# SCH_Atari_ST_sidecart_prototype_shared_b.net
KiCad netlist of a schematic drawn in EasyEDA
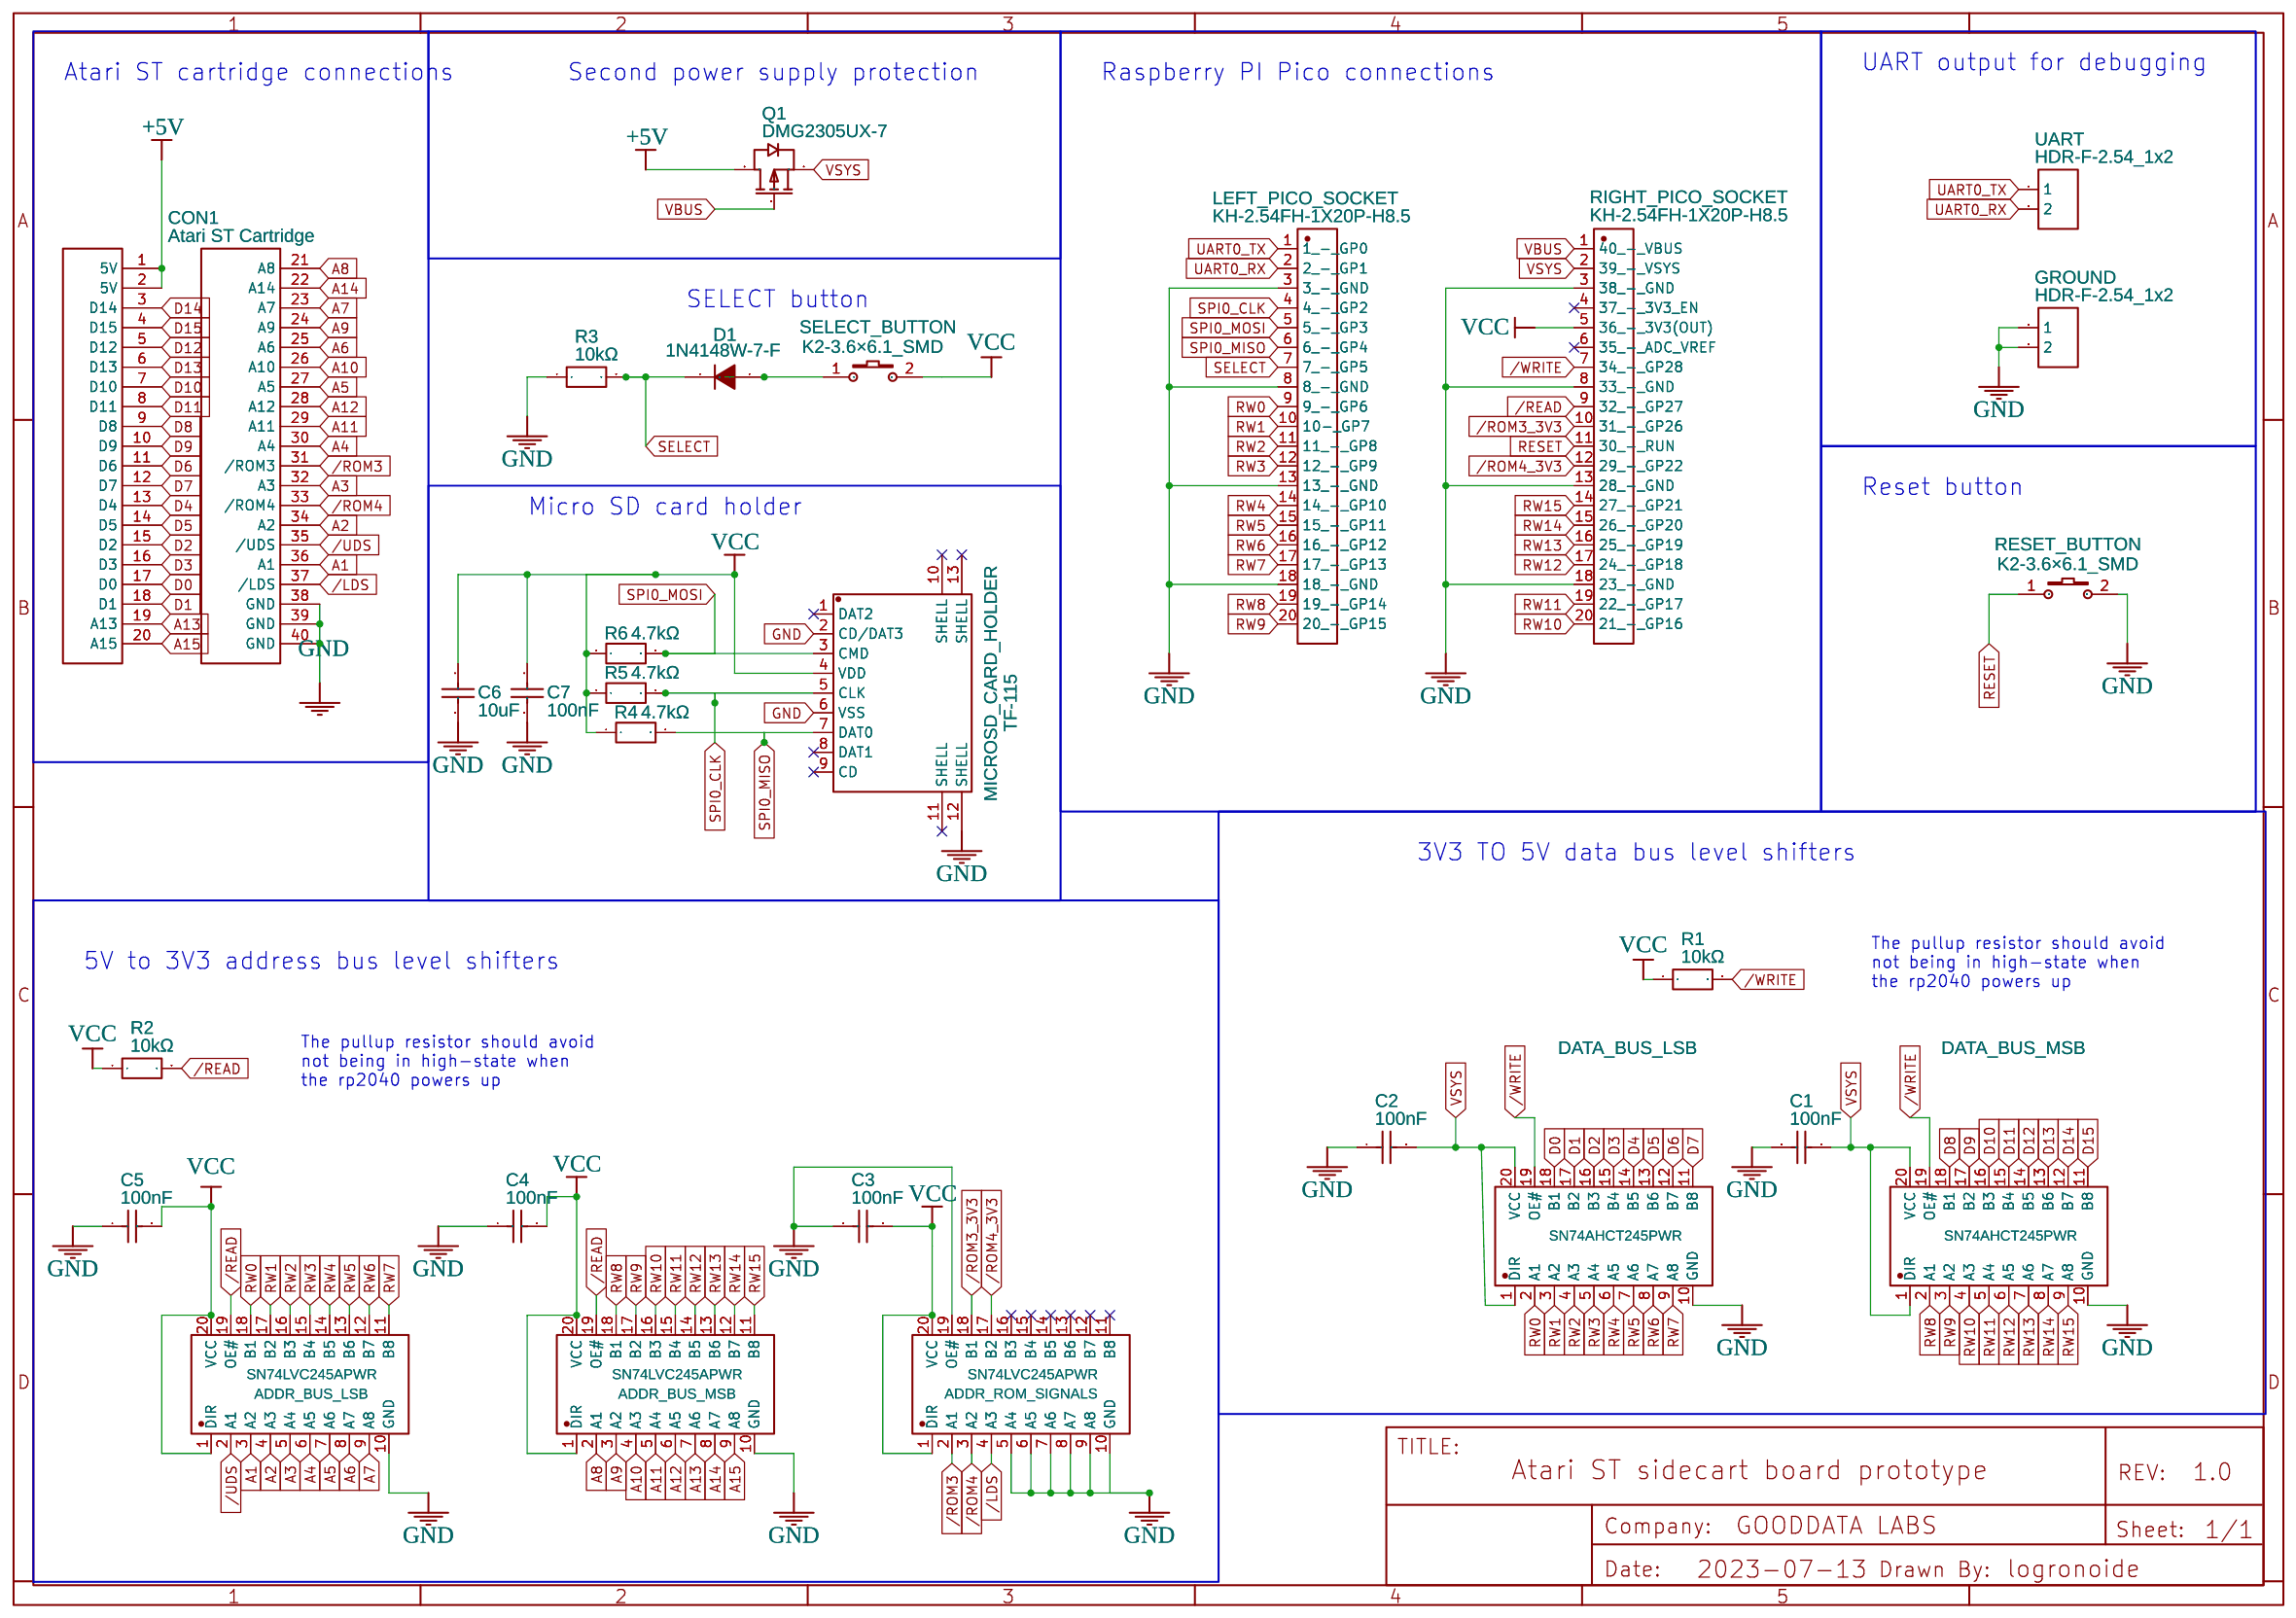
[diagram p0: schematic sheet]

(export (version "E")
  (design (tool "Eeschema 10.0.6"))
  (components
    (comp (ref "ADDR_BUS_LSB")
      (value "SN74LVC245APWR")
      (fields (field (name "Manufacturer") "TI(德州仪器)"))
      (libsource (lib "") (part "SN74LVC245ANG4_2"))
    )
    (comp (ref "ADDR_BUS_MSB")
      (value "SN74LVC245APWR")
      (fields (field (name "Manufacturer") "TI(德州仪器)"))
      (libsource (lib "") (part "SN74LVC245ANG4_1"))
    )
    (comp (ref "ADDR_ROM_SIGNALS")
      (value "SN74LVC245APWR")
      (fields (field (name "Manufacturer") "TI(德州仪器)"))
      (libsource (lib "") (part "SN74LVC245ANG4"))
    )
    (comp (ref "C1")
      (value "100nF")
      (fields
        (field (name "Manufacturer Part") "C0603C104K5RACAUTO")
        (field (name "Manufacturer") "KEMET(基美)")
      )
      (libsource (lib "") (part "C0603C104K5RACAUTO"))
    )
    (comp (ref "C2")
      (value "100nF")
      (fields
        (field (name "Manufacturer Part") "C0603C104K5RACAUTO")
        (field (name "Manufacturer") "KEMET(基美)")
      )
      (libsource (lib "") (part "C0603C104K5RACAUTO"))
    )
    (comp (ref "C3")
      (value "100nF")
      (fields
        (field (name "Manufacturer Part") "C0603C104K5RACAUTO")
        (field (name "Manufacturer") "KEMET(基美)")
      )
      (libsource (lib "") (part "C0603C104K5RACAUTO"))
    )
    (comp (ref "C4")
      (value "100nF")
      (fields
        (field (name "Manufacturer Part") "C0603C104K5RACAUTO")
        (field (name "Manufacturer") "KEMET(基美)")
      )
      (libsource (lib "") (part "C0603C104K5RACAUTO"))
    )
    (comp (ref "C5")
      (value "100nF")
      (fields
        (field (name "Manufacturer Part") "C0603C104K5RACAUTO")
        (field (name "Manufacturer") "KEMET(基美)")
      )
      (libsource (lib "") (part "C0603C104K5RACAUTO"))
    )
    (comp (ref "C6")
      (value "10uF")
      (fields
        (field (name "Manufacturer Part") "CC0603MRX5R7BB106")
        (field (name "Manufacturer") "YAGEO(国巨)")
      )
      (libsource (lib "") (part "CC0603MRX5R7BB106"))
    )
    (comp (ref "C7")
      (value "100nF")
      (fields
        (field (name "Manufacturer Part") "C0603C104K5RACAUTO")
        (field (name "Manufacturer") "KEMET(基美)")
      )
      (libsource (lib "") (part "C0603C104K5RACAUTO_1"))
    )
    (comp (ref "CON1") (value "Atari ST Cartridge") (libsource (lib "") (part "Unknown_90_-590")))
    (comp (ref "D1")
      (value "1N4148W-7-F")
      (fields (field (name "Manufacturer") "DIODES(美台)"))
      (libsource (lib "") (part "1N4148W-7-F"))
    )
    (comp (ref "DATA_BUS_LSB")
      (value "SN74AHCT245PWR")
      (fields (field (name "Manufacturer") "TI(德州仪器)"))
      (libsource (lib "") (part "SN74AHCT245N_1"))
    )
    (comp (ref "DATA_BUS_MSB")
      (value "SN74AHCT245PWR")
      (fields (field (name "Manufacturer") "TI(德州仪器)"))
      (libsource (lib "") (part "SN74AHCT245N"))
    )
    (comp (ref "GROUND") (value "HDR-F-2.54_1x2") (libsource (lib "") (part "HDR-F-2.54_1x2")))
    (comp (ref "LEFT_PICO_SOCKET")
      (value "KH-2.54FH-1X20P-H8.5")
      (fields (field (name "Manufacturer") "kinghelm(金航标)"))
      (libsource (lib "") (part "KH-2.54FH-1X20P-H8.5_1"))
    )
    (comp (ref "MICROSD_CARD_HOLDER")
      (value "TF-115")
      (fields (field (name "Manufacturer") "XUNPU(讯普)"))
      (libsource (lib "") (part "TF-115"))
    )
    (comp (ref "Q1")
      (value "DMG2305UX-7")
      (fields (field (name "Manufacturer") "DIODES(美台)"))
      (libsource (lib "") (part "DMG2305UX-7"))
    )
    (comp (ref "R1")
      (value "10kΩ")
      (fields (field (name "Manufacturer Part") "RT0603DRE0710KL") (field (name "Manufacturer") "YAGEO(国巨)"))
      (libsource (lib "") (part "RT0603DRE0710KL"))
    )
    (comp (ref "R2")
      (value "10kΩ")
      (fields (field (name "Manufacturer Part") "RT0603DRE0710KL") (field (name "Manufacturer") "YAGEO(国巨)"))
      (libsource (lib "") (part "RT0603DRE0710KL"))
    )
    (comp (ref "R3")
      (value "10kΩ")
      (fields (field (name "Manufacturer Part") "RT0603DRE0710KL") (field (name "Manufacturer") "YAGEO(国巨)"))
      (libsource (lib "") (part "RT0603DRE0710KL"))
    )
    (comp (ref "R4")
      (value "4.7kΩ")
      (fields
        (field (name "Manufacturer Part") "CR0603F4K70P05Z")
        (field (name "Manufacturer") "EVER OHMS(天二科技)")
      )
      (libsource (lib "") (part "CR0603F4K70P05Z"))
    )
    (comp (ref "R5")
      (value "4.7kΩ")
      (fields
        (field (name "Manufacturer Part") "CR0603F4K70P05Z")
        (field (name "Manufacturer") "EVER OHMS(天二科技)")
      )
      (libsource (lib "") (part "CR0603F4K70P05Z"))
    )
    (comp (ref "R6")
      (value "4.7kΩ")
      (fields
        (field (name "Manufacturer Part") "CR0603F4K70P05Z")
        (field (name "Manufacturer") "EVER OHMS(天二科技)")
      )
      (libsource (lib "") (part "CR0603F4K70P05Z"))
    )
    (comp (ref "RESET_BUTTON")
      (value "K2-3.6×6.1_SMD")
      (fields (field (name "Manufacturer Part") "K2-1107ST-A4SW-06"))
      (libsource (lib "") (part "K2-3.6×6.1_SMD_1"))
    )
    (comp (ref "RIGHT_PICO_SOCKET")
      (value "KH-2.54FH-1X20P-H8.5")
      (fields (field (name "Manufacturer") "kinghelm(金航标)"))
      (libsource (lib "") (part "KH-2.54FH-1X20P-H8.5"))
    )
    (comp (ref "SELECT_BUTTON")
      (value "K2-3.6×6.1_SMD")
      (fields (field (name "Manufacturer Part") "K2-1107ST-A4SW-06"))
      (libsource (lib "") (part "K2-3.6×6.1_SMD"))
    )
    (comp (ref "UART") (value "HDR-F-2.54_1x2") (libsource (lib "") (part "HDR-F-2.54_1x2_1")))
  )
  (nets
    (net (code "1") (name "+5V") (class "Default")
      (node (ref "CON1") (pin "1") (pinfunction "5V_1") (pintype "unspecified"))
      (node (ref "CON1") (pin "2") (pinfunction "5V_2") (pintype "unspecified"))
      (node (ref "Q1") (pin "3") (pinfunction "D_3") (pintype "unspecified"))
    )
    (net (code "2") (name "A1") (class "Default")
      (node (ref "ADDR_BUS_LSB") (pin "3") (pinfunction "A2_3") (pintype "unspecified"))
      (node (ref "CON1") (pin "36") (pinfunction "A1_36") (pintype "unspecified"))
    )
    (net (code "3") (name "A2") (class "Default")
      (node (ref "ADDR_BUS_LSB") (pin "4") (pinfunction "A3_4") (pintype "unspecified"))
      (node (ref "CON1") (pin "34") (pinfunction "A2_34") (pintype "unspecified"))
    )
    (net (code "4") (name "A3") (class "Default")
      (node (ref "ADDR_BUS_LSB") (pin "5") (pinfunction "A4_5") (pintype "unspecified"))
      (node (ref "CON1") (pin "32") (pinfunction "A3_32") (pintype "unspecified"))
    )
    (net (code "5") (name "A4") (class "Default")
      (node (ref "ADDR_BUS_LSB") (pin "6") (pinfunction "A5_6") (pintype "unspecified"))
      (node (ref "CON1") (pin "30") (pinfunction "A4_30") (pintype "unspecified"))
    )
    (net (code "6") (name "A5") (class "Default")
      (node (ref "ADDR_BUS_LSB") (pin "7") (pinfunction "A6_7") (pintype "unspecified"))
      (node (ref "CON1") (pin "27") (pinfunction "A5_27") (pintype "unspecified"))
    )
    (net (code "7") (name "A6") (class "Default")
      (node (ref "ADDR_BUS_LSB") (pin "8") (pinfunction "A7_8") (pintype "unspecified"))
      (node (ref "CON1") (pin "25") (pinfunction "A6_25") (pintype "unspecified"))
    )
    (net (code "8") (name "A7") (class "Default")
      (node (ref "ADDR_BUS_LSB") (pin "9") (pinfunction "A8_9") (pintype "unspecified"))
      (node (ref "CON1") (pin "23") (pinfunction "A7_23") (pintype "unspecified"))
    )
    (net (code "9") (name "A8") (class "Default")
      (node (ref "ADDR_BUS_MSB") (pin "2") (pinfunction "A1_2") (pintype "unspecified"))
      (node (ref "CON1") (pin "21") (pinfunction "A8_21") (pintype "unspecified"))
    )
    (net (code "10") (name "A9") (class "Default")
      (node (ref "ADDR_BUS_MSB") (pin "3") (pinfunction "A2_3") (pintype "unspecified"))
      (node (ref "CON1") (pin "24") (pinfunction "A9_24") (pintype "unspecified"))
    )
    (net (code "11") (name "A10") (class "Default")
      (node (ref "ADDR_BUS_MSB") (pin "4") (pinfunction "A3_4") (pintype "unspecified"))
      (node (ref "CON1") (pin "26") (pinfunction "A10_26") (pintype "unspecified"))
    )
    (net (code "12") (name "A11") (class "Default")
      (node (ref "ADDR_BUS_MSB") (pin "5") (pinfunction "A4_5") (pintype "unspecified"))
      (node (ref "CON1") (pin "29") (pinfunction "A11_29") (pintype "unspecified"))
    )
    (net (code "13") (name "A12") (class "Default")
      (node (ref "ADDR_BUS_MSB") (pin "6") (pinfunction "A5_6") (pintype "unspecified"))
      (node (ref "CON1") (pin "28") (pinfunction "A12_28") (pintype "unspecified"))
    )
    (net (code "14") (name "A13") (class "Default")
      (node (ref "ADDR_BUS_MSB") (pin "7") (pinfunction "A6_7") (pintype "unspecified"))
      (node (ref "CON1") (pin "19") (pinfunction "A13_19") (pintype "unspecified"))
    )
    (net (code "15") (name "A14") (class "Default")
      (node (ref "ADDR_BUS_MSB") (pin "8") (pinfunction "A7_8") (pintype "unspecified"))
      (node (ref "CON1") (pin "22") (pinfunction "A14_22") (pintype "unspecified"))
    )
    (net (code "16") (name "A15") (class "Default")
      (node (ref "ADDR_BUS_MSB") (pin "9") (pinfunction "A8_9") (pintype "unspecified"))
      (node (ref "CON1") (pin "20") (pinfunction "A15_20") (pintype "unspecified"))
    )
    (net (code "17") (name "D0") (class "Default")
      (node (ref "CON1") (pin "17") (pinfunction "D0_17") (pintype "unspecified"))
      (node (ref "DATA_BUS_LSB") (pin "18") (pinfunction "B1_18") (pintype "unspecified"))
    )
    (net (code "18") (name "D1") (class "Default")
      (node (ref "CON1") (pin "18") (pinfunction "D1_18") (pintype "unspecified"))
      (node (ref "DATA_BUS_LSB") (pin "17") (pinfunction "B2_17") (pintype "unspecified"))
    )
    (net (code "19") (name "D2") (class "Default")
      (node (ref "CON1") (pin "15") (pinfunction "D2_15") (pintype "unspecified"))
      (node (ref "DATA_BUS_LSB") (pin "16") (pinfunction "B3_16") (pintype "unspecified"))
    )
    (net (code "20") (name "D3") (class "Default")
      (node (ref "CON1") (pin "16") (pinfunction "D3_16") (pintype "unspecified"))
      (node (ref "DATA_BUS_LSB") (pin "15") (pinfunction "B4_15") (pintype "unspecified"))
    )
    (net (code "21") (name "D4") (class "Default")
      (node (ref "CON1") (pin "13") (pinfunction "D4_13") (pintype "unspecified"))
      (node (ref "DATA_BUS_LSB") (pin "14") (pinfunction "B5_14") (pintype "unspecified"))
    )
    (net (code "22") (name "D5") (class "Default")
      (node (ref "CON1") (pin "14") (pinfunction "D5_14") (pintype "unspecified"))
      (node (ref "DATA_BUS_LSB") (pin "13") (pinfunction "B6_13") (pintype "unspecified"))
    )
    (net (code "23") (name "D6") (class "Default")
      (node (ref "CON1") (pin "11") (pinfunction "D6_11") (pintype "unspecified"))
      (node (ref "DATA_BUS_LSB") (pin "12") (pinfunction "B7_12") (pintype "unspecified"))
    )
    (net (code "24") (name "D7") (class "Default")
      (node (ref "CON1") (pin "12") (pinfunction "D7_12") (pintype "unspecified"))
      (node (ref "DATA_BUS_LSB") (pin "11") (pinfunction "B8_11") (pintype "unspecified"))
    )
    (net (code "25") (name "D8") (class "Default")
      (node (ref "CON1") (pin "9") (pinfunction "D8_9") (pintype "unspecified"))
      (node (ref "DATA_BUS_MSB") (pin "18") (pinfunction "B1_18") (pintype "unspecified"))
    )
    (net (code "26") (name "D9") (class "Default")
      (node (ref "CON1") (pin "10") (pinfunction "D9_10") (pintype "unspecified"))
      (node (ref "DATA_BUS_MSB") (pin "17") (pinfunction "B2_17") (pintype "unspecified"))
    )
    (net (code "27") (name "D10") (class "Default")
      (node (ref "CON1") (pin "7") (pinfunction "D10_7") (pintype "unspecified"))
      (node (ref "DATA_BUS_MSB") (pin "16") (pinfunction "B3_16") (pintype "unspecified"))
    )
    (net (code "28") (name "D11") (class "Default")
      (node (ref "CON1") (pin "8") (pinfunction "D11_8") (pintype "unspecified"))
      (node (ref "DATA_BUS_MSB") (pin "15") (pinfunction "B4_15") (pintype "unspecified"))
    )
    (net (code "29") (name "D12") (class "Default")
      (node (ref "CON1") (pin "5") (pinfunction "D12_5") (pintype "unspecified"))
      (node (ref "DATA_BUS_MSB") (pin "14") (pinfunction "B5_14") (pintype "unspecified"))
    )
    (net (code "30") (name "D13") (class "Default")
      (node (ref "CON1") (pin "6") (pinfunction "D13_6") (pintype "unspecified"))
      (node (ref "DATA_BUS_MSB") (pin "13") (pinfunction "B6_13") (pintype "unspecified"))
    )
    (net (code "31") (name "D14") (class "Default")
      (node (ref "CON1") (pin "3") (pinfunction "D14_3") (pintype "unspecified"))
      (node (ref "DATA_BUS_MSB") (pin "12") (pinfunction "B7_12") (pintype "unspecified"))
    )
    (net (code "32") (name "D15") (class "Default")
      (node (ref "CON1") (pin "4") (pinfunction "D15_4") (pintype "unspecified"))
      (node (ref "DATA_BUS_MSB") (pin "11") (pinfunction "B8_11") (pintype "unspecified"))
    )
    (net (code "33") (name "GND") (class "Default")
      (node (ref "ADDR_BUS_LSB") (pin "10") (pinfunction "GND_10") (pintype "unspecified"))
      (node (ref "ADDR_BUS_MSB") (pin "10") (pinfunction "GND_10") (pintype "unspecified"))
      (node (ref "ADDR_ROM_SIGNALS") (pin "10") (pinfunction "GND_10") (pintype "unspecified"))
      (node (ref "ADDR_ROM_SIGNALS") (pin "19") (pinfunction "OE#_19") (pintype "unspecified"))
      (node (ref "ADDR_ROM_SIGNALS") (pin "5") (pinfunction "A4_5") (pintype "unspecified"))
      (node (ref "ADDR_ROM_SIGNALS") (pin "6") (pinfunction "A5_6") (pintype "unspecified"))
      (node (ref "ADDR_ROM_SIGNALS") (pin "7") (pinfunction "A6_7") (pintype "unspecified"))
      (node (ref "ADDR_ROM_SIGNALS") (pin "8") (pinfunction "A7_8") (pintype "unspecified"))
      (node (ref "ADDR_ROM_SIGNALS") (pin "9") (pinfunction "A8_9") (pintype "unspecified"))
      (node (ref "C1") (pin "1") (pinfunction "1_1") (pintype "input"))
      (node (ref "C2") (pin "1") (pinfunction "1_1") (pintype "input"))
      (node (ref "C3") (pin "1") (pinfunction "1_1") (pintype "input"))
      (node (ref "C4") (pin "1") (pinfunction "1_1") (pintype "input"))
      (node (ref "C5") (pin "1") (pinfunction "1_1") (pintype "input"))
      (node (ref "C6") (pin "1") (pinfunction "1_1") (pintype "input"))
      (node (ref "C7") (pin "1") (pinfunction "1_1") (pintype "input"))
      (node (ref "CON1") (pin "38") (pinfunction "GND_38") (pintype "unspecified"))
      (node (ref "CON1") (pin "39") (pinfunction "GND_39") (pintype "unspecified"))
      (node (ref "CON1") (pin "40") (pinfunction "GND_40") (pintype "unspecified"))
      (node (ref "DATA_BUS_LSB") (pin "10") (pinfunction "GND_10") (pintype "unspecified"))
      (node (ref "DATA_BUS_MSB") (pin "10") (pinfunction "GND_10") (pintype "unspecified"))
      (node (ref "GROUND") (pin "1") (pinfunction "1_1") (pintype "input"))
      (node (ref "GROUND") (pin "2") (pinfunction "2_2") (pintype "input"))
      (node (ref "LEFT_PICO_SOCKET") (pin "13") (pinfunction "13_-_GND_13") (pintype "unspecified"))
      (node (ref "LEFT_PICO_SOCKET") (pin "18") (pinfunction "18_-_GND_18") (pintype "unspecified"))
      (node (ref "LEFT_PICO_SOCKET") (pin "3") (pinfunction "3_-_GND_3") (pintype "unspecified"))
      (node (ref "LEFT_PICO_SOCKET") (pin "8") (pinfunction "8_-_GND_8") (pintype "unspecified"))
      (node (ref "MICROSD_CARD_HOLDER") (pin "12") (pinfunction "SHELL_12") (pintype "unspecified"))
      (node (ref "MICROSD_CARD_HOLDER") (pin "2") (pinfunction "CD/DAT3_2") (pintype "unspecified"))
      (node (ref "MICROSD_CARD_HOLDER") (pin "6") (pinfunction "VSS_6") (pintype "unspecified"))
      (node (ref "R3") (pin "1") (pinfunction "1_1") (pintype "unspecified"))
      (node (ref "RESET_BUTTON") (pin "2") (pinfunction "2_2") (pintype "unspecified"))
      (node (ref "RIGHT_PICO_SOCKET") (pin "13") (pinfunction "28_-_GND_13") (pintype "unspecified"))
      (node (ref "RIGHT_PICO_SOCKET") (pin "18") (pinfunction "23_-_GND_18") (pintype "unspecified"))
      (node (ref "RIGHT_PICO_SOCKET") (pin "3") (pinfunction "38_-_GND_3") (pintype "unspecified"))
      (node (ref "RIGHT_PICO_SOCKET") (pin "8") (pinfunction "33_-_GND_8") (pintype "unspecified"))
    )
    (net (code "34") (name "Net-(D1-A)") (class "Default")
      (node (ref "D1") (pin "2") (pinfunction "A_2") (pintype "unspecified"))
      (node (ref "SELECT_BUTTON") (pin "1") (pinfunction "1_1") (pintype "unspecified"))
    )
    (net (code "35") (name "RESET") (class "Default")
      (node (ref "RESET_BUTTON") (pin "1") (pinfunction "1_1") (pintype "unspecified"))
      (node (ref "RIGHT_PICO_SOCKET") (pin "11") (pinfunction "30_-_RUN_11") (pintype "unspecified"))
    )
    (net (code "36") (name "RW0") (class "Default")
      (node (ref "ADDR_BUS_LSB") (pin "18") (pinfunction "B1_18") (pintype "unspecified"))
      (node (ref "DATA_BUS_LSB") (pin "2") (pinfunction "A1_2") (pintype "unspecified"))
      (node (ref "LEFT_PICO_SOCKET") (pin "9") (pinfunction "9_-_GP6_9") (pintype "unspecified"))
    )
    (net (code "37") (name "RW1") (class "Default")
      (node (ref "ADDR_BUS_LSB") (pin "17") (pinfunction "B2_17") (pintype "unspecified"))
      (node (ref "DATA_BUS_LSB") (pin "3") (pinfunction "A2_3") (pintype "unspecified"))
      (node (ref "LEFT_PICO_SOCKET") (pin "10") (pinfunction "10-_GP7_10") (pintype "unspecified"))
    )
    (net (code "38") (name "RW2") (class "Default")
      (node (ref "ADDR_BUS_LSB") (pin "16") (pinfunction "B3_16") (pintype "unspecified"))
      (node (ref "DATA_BUS_LSB") (pin "4") (pinfunction "A3_4") (pintype "unspecified"))
      (node (ref "LEFT_PICO_SOCKET") (pin "11") (pinfunction "11_-_GP8_11") (pintype "unspecified"))
    )
    (net (code "39") (name "RW3") (class "Default")
      (node (ref "ADDR_BUS_LSB") (pin "15") (pinfunction "B4_15") (pintype "unspecified"))
      (node (ref "DATA_BUS_LSB") (pin "5") (pinfunction "A4_5") (pintype "unspecified"))
      (node (ref "LEFT_PICO_SOCKET") (pin "12") (pinfunction "12_-_GP9_12") (pintype "unspecified"))
    )
    (net (code "40") (name "RW4") (class "Default")
      (node (ref "ADDR_BUS_LSB") (pin "14") (pinfunction "B5_14") (pintype "unspecified"))
      (node (ref "DATA_BUS_LSB") (pin "6") (pinfunction "A5_6") (pintype "unspecified"))
      (node (ref "LEFT_PICO_SOCKET") (pin "14") (pinfunction "14_-_GP10_14") (pintype "unspecified"))
    )
    (net (code "41") (name "RW5") (class "Default")
      (node (ref "ADDR_BUS_LSB") (pin "13") (pinfunction "B6_13") (pintype "unspecified"))
      (node (ref "DATA_BUS_LSB") (pin "7") (pinfunction "A6_7") (pintype "unspecified"))
      (node (ref "LEFT_PICO_SOCKET") (pin "15") (pinfunction "15_-_GP11_15") (pintype "unspecified"))
    )
    (net (code "42") (name "RW6") (class "Default")
      (node (ref "ADDR_BUS_LSB") (pin "12") (pinfunction "B7_12") (pintype "unspecified"))
      (node (ref "DATA_BUS_LSB") (pin "8") (pinfunction "A7_8") (pintype "unspecified"))
      (node (ref "LEFT_PICO_SOCKET") (pin "16") (pinfunction "16_-_GP12_16") (pintype "unspecified"))
    )
    (net (code "43") (name "RW7") (class "Default")
      (node (ref "ADDR_BUS_LSB") (pin "11") (pinfunction "B8_11") (pintype "unspecified"))
      (node (ref "DATA_BUS_LSB") (pin "9") (pinfunction "A8_9") (pintype "unspecified"))
      (node (ref "LEFT_PICO_SOCKET") (pin "17") (pinfunction "17_-_GP13_17") (pintype "unspecified"))
    )
    (net (code "44") (name "RW8") (class "Default")
      (node (ref "ADDR_BUS_MSB") (pin "18") (pinfunction "B1_18") (pintype "unspecified"))
      (node (ref "DATA_BUS_MSB") (pin "2") (pinfunction "A1_2") (pintype "unspecified"))
      (node (ref "LEFT_PICO_SOCKET") (pin "19") (pinfunction "19_-_GP14_19") (pintype "unspecified"))
    )
    (net (code "45") (name "RW9") (class "Default")
      (node (ref "ADDR_BUS_MSB") (pin "17") (pinfunction "B2_17") (pintype "unspecified"))
      (node (ref "DATA_BUS_MSB") (pin "3") (pinfunction "A2_3") (pintype "unspecified"))
      (node (ref "LEFT_PICO_SOCKET") (pin "20") (pinfunction "20_-_GP15_20") (pintype "unspecified"))
    )
    (net (code "46") (name "RW10") (class "Default")
      (node (ref "ADDR_BUS_MSB") (pin "16") (pinfunction "B3_16") (pintype "unspecified"))
      (node (ref "DATA_BUS_MSB") (pin "4") (pinfunction "A3_4") (pintype "unspecified"))
      (node (ref "RIGHT_PICO_SOCKET") (pin "20") (pinfunction "21_-_GP16_20") (pintype "unspecified"))
    )
    (net (code "47") (name "RW11") (class "Default")
      (node (ref "ADDR_BUS_MSB") (pin "15") (pinfunction "B4_15") (pintype "unspecified"))
      (node (ref "DATA_BUS_MSB") (pin "5") (pinfunction "A4_5") (pintype "unspecified"))
      (node (ref "RIGHT_PICO_SOCKET") (pin "19") (pinfunction "22_-_GP17_19") (pintype "unspecified"))
    )
    (net (code "48") (name "RW12") (class "Default")
      (node (ref "ADDR_BUS_MSB") (pin "14") (pinfunction "B5_14") (pintype "unspecified"))
      (node (ref "DATA_BUS_MSB") (pin "6") (pinfunction "A5_6") (pintype "unspecified"))
      (node (ref "RIGHT_PICO_SOCKET") (pin "17") (pinfunction "24_-_GP18_17") (pintype "unspecified"))
    )
    (net (code "49") (name "RW13") (class "Default")
      (node (ref "ADDR_BUS_MSB") (pin "13") (pinfunction "B6_13") (pintype "unspecified"))
      (node (ref "DATA_BUS_MSB") (pin "7") (pinfunction "A6_7") (pintype "unspecified"))
      (node (ref "RIGHT_PICO_SOCKET") (pin "16") (pinfunction "25_-_GP19_16") (pintype "unspecified"))
    )
    (net (code "50") (name "RW14") (class "Default")
      (node (ref "ADDR_BUS_MSB") (pin "12") (pinfunction "B7_12") (pintype "unspecified"))
      (node (ref "DATA_BUS_MSB") (pin "8") (pinfunction "A7_8") (pintype "unspecified"))
      (node (ref "RIGHT_PICO_SOCKET") (pin "15") (pinfunction "26_-_GP20_15") (pintype "unspecified"))
    )
    (net (code "51") (name "RW15") (class "Default")
      (node (ref "ADDR_BUS_MSB") (pin "11") (pinfunction "B8_11") (pintype "unspecified"))
      (node (ref "DATA_BUS_MSB") (pin "9") (pinfunction "A8_9") (pintype "unspecified"))
      (node (ref "RIGHT_PICO_SOCKET") (pin "14") (pinfunction "27_-_GP21_14") (pintype "unspecified"))
    )
    (net (code "52") (name "SELECT") (class "Default")
      (node (ref "D1") (pin "1") (pinfunction "C_1") (pintype "unspecified"))
      (node (ref "LEFT_PICO_SOCKET") (pin "7") (pinfunction "7_-_GP5_7") (pintype "unspecified"))
      (node (ref "R3") (pin "2") (pinfunction "2_2") (pintype "unspecified"))
    )
    (net (code "53") (name "SPI0_CLK") (class "Default")
      (node (ref "LEFT_PICO_SOCKET") (pin "4") (pinfunction "4_-_GP2_4") (pintype "unspecified"))
      (node (ref "MICROSD_CARD_HOLDER") (pin "5") (pinfunction "CLK_5") (pintype "unspecified"))
      (node (ref "R5") (pin "2") (pinfunction "2_2") (pintype "unspecified"))
    )
    (net (code "54") (name "SPI0_MISO") (class "Default")
      (node (ref "LEFT_PICO_SOCKET") (pin "6") (pinfunction "6_-_GP4_6") (pintype "unspecified"))
      (node (ref "MICROSD_CARD_HOLDER") (pin "7") (pinfunction "DAT0_7") (pintype "unspecified"))
      (node (ref "R4") (pin "2") (pinfunction "2_2") (pintype "unspecified"))
    )
    (net (code "55") (name "SPI0_MOSI") (class "Default")
      (node (ref "LEFT_PICO_SOCKET") (pin "5") (pinfunction "5_-_GP3_5") (pintype "unspecified"))
      (node (ref "MICROSD_CARD_HOLDER") (pin "3") (pinfunction "CMD_3") (pintype "unspecified"))
      (node (ref "R6") (pin "2") (pinfunction "2_2") (pintype "unspecified"))
    )
    (net (code "56") (name "UART0_RX") (class "Default")
      (node (ref "LEFT_PICO_SOCKET") (pin "2") (pinfunction "2_-_GP1_2") (pintype "unspecified"))
      (node (ref "UART") (pin "2") (pinfunction "2_2") (pintype "input"))
    )
    (net (code "57") (name "UART0_TX") (class "Default")
      (node (ref "LEFT_PICO_SOCKET") (pin "1") (pinfunction "1_-_GP0_1") (pintype "unspecified"))
      (node (ref "UART") (pin "1") (pinfunction "1_1") (pintype "input"))
    )
    (net (code "58") (name "VBUS") (class "Default")
      (node (ref "Q1") (pin "1") (pinfunction "G_1") (pintype "unspecified"))
      (node (ref "RIGHT_PICO_SOCKET") (pin "1") (pinfunction "40_-_VBUS_1") (pintype "unspecified"))
    )
    (net (code "59") (name "VCC") (class "Default")
      (node (ref "ADDR_BUS_LSB") (pin "1") (pinfunction "DIR_1") (pintype "unspecified"))
      (node (ref "ADDR_BUS_LSB") (pin "20") (pinfunction "VCC_20") (pintype "unspecified"))
      (node (ref "ADDR_BUS_MSB") (pin "1") (pinfunction "DIR_1") (pintype "unspecified"))
      (node (ref "ADDR_BUS_MSB") (pin "20") (pinfunction "VCC_20") (pintype "unspecified"))
      (node (ref "ADDR_ROM_SIGNALS") (pin "1") (pinfunction "DIR_1") (pintype "unspecified"))
      (node (ref "ADDR_ROM_SIGNALS") (pin "20") (pinfunction "VCC_20") (pintype "unspecified"))
      (node (ref "C3") (pin "2") (pinfunction "2_2") (pintype "input"))
      (node (ref "C4") (pin "2") (pinfunction "2_2") (pintype "input"))
      (node (ref "C5") (pin "2") (pinfunction "2_2") (pintype "input"))
      (node (ref "C6") (pin "2") (pinfunction "2_2") (pintype "input"))
      (node (ref "C7") (pin "2") (pinfunction "2_2") (pintype "input"))
      (node (ref "MICROSD_CARD_HOLDER") (pin "4") (pinfunction "VDD_4") (pintype "unspecified"))
      (node (ref "R1") (pin "1") (pinfunction "1_1") (pintype "unspecified"))
      (node (ref "R2") (pin "1") (pinfunction "1_1") (pintype "unspecified"))
      (node (ref "R4") (pin "1") (pinfunction "1_1") (pintype "unspecified"))
      (node (ref "R5") (pin "1") (pinfunction "1_1") (pintype "unspecified"))
      (node (ref "R6") (pin "1") (pinfunction "1_1") (pintype "unspecified"))
      (node (ref "RIGHT_PICO_SOCKET") (pin "5") (pinfunction "36_-_3V3(OUT)_5") (pintype "unspecified"))
      (node (ref "SELECT_BUTTON") (pin "2") (pinfunction "2_2") (pintype "unspecified"))
    )
    (net (code "60") (name "VSYS") (class "Default")
      (node (ref "C1") (pin "2") (pinfunction "2_2") (pintype "input"))
      (node (ref "C2") (pin "2") (pinfunction "2_2") (pintype "input"))
      (node (ref "DATA_BUS_LSB") (pin "1") (pinfunction "DIR_1") (pintype "unspecified"))
      (node (ref "DATA_BUS_LSB") (pin "20") (pinfunction "VCC_20") (pintype "unspecified"))
      (node (ref "DATA_BUS_MSB") (pin "1") (pinfunction "DIR_1") (pintype "unspecified"))
      (node (ref "DATA_BUS_MSB") (pin "20") (pinfunction "VCC_20") (pintype "unspecified"))
      (node (ref "Q1") (pin "2") (pinfunction "S_2") (pintype "unspecified"))
      (node (ref "RIGHT_PICO_SOCKET") (pin "2") (pinfunction "39_-_VSYS_2") (pintype "unspecified"))
    )
    (net (code "61") (name "unconnected-(ADDR_ROM_SIGNALS-B3-Pad16)") (class "Default")
      (node (ref "ADDR_ROM_SIGNALS") (pin "16") (pinfunction "B3_16") (pintype "unspecified+no_connect"))
    )
    (net (code "62") (name "unconnected-(ADDR_ROM_SIGNALS-B4-Pad15)") (class "Default")
      (node (ref "ADDR_ROM_SIGNALS") (pin "15") (pinfunction "B4_15") (pintype "unspecified+no_connect"))
    )
    (net (code "63") (name "unconnected-(ADDR_ROM_SIGNALS-B5-Pad14)") (class "Default")
      (node (ref "ADDR_ROM_SIGNALS") (pin "14") (pinfunction "B5_14") (pintype "unspecified+no_connect"))
    )
    (net (code "64") (name "unconnected-(ADDR_ROM_SIGNALS-B6-Pad13)") (class "Default")
      (node (ref "ADDR_ROM_SIGNALS") (pin "13") (pinfunction "B6_13") (pintype "unspecified+no_connect"))
    )
    (net (code "65") (name "unconnected-(ADDR_ROM_SIGNALS-B7-Pad12)") (class "Default")
      (node (ref "ADDR_ROM_SIGNALS") (pin "12") (pinfunction "B7_12") (pintype "unspecified+no_connect"))
    )
    (net (code "66") (name "unconnected-(ADDR_ROM_SIGNALS-B8-Pad11)") (class "Default")
      (node (ref "ADDR_ROM_SIGNALS") (pin "11") (pinfunction "B8_11") (pintype "unspecified+no_connect"))
    )
    (net (code "67") (name "unconnected-(MICROSD_CARD_HOLDER-CD-Pad9)") (class "Default")
      (node (ref "MICROSD_CARD_HOLDER") (pin "9") (pinfunction "CD_9") (pintype "unspecified+no_connect"))
    )
    (net (code "68") (name "unconnected-(MICROSD_CARD_HOLDER-DAT1-Pad8)") (class "Default")
      (node (ref "MICROSD_CARD_HOLDER") (pin "8") (pinfunction "DAT1_8") (pintype "unspecified+no_connect"))
    )
    (net (code "69") (name "unconnected-(MICROSD_CARD_HOLDER-DAT2-Pad1)") (class "Default")
      (node (ref "MICROSD_CARD_HOLDER") (pin "1") (pinfunction "DAT2_1") (pintype "unspecified+no_connect"))
    )
    (net (code "70") (name "unconnected-(MICROSD_CARD_HOLDER-SHELL-Pad10)") (class "Default")
      (node (ref "MICROSD_CARD_HOLDER") (pin "10") (pinfunction "SHELL_10") (pintype "unspecified+no_connect"))
    )
    (net (code "71") (name "unconnected-(MICROSD_CARD_HOLDER-SHELL-Pad11)") (class "Default")
      (node (ref "MICROSD_CARD_HOLDER") (pin "11") (pinfunction "SHELL_11") (pintype "unspecified+no_connect"))
    )
    (net (code "72") (name "unconnected-(MICROSD_CARD_HOLDER-SHELL-Pad13)") (class "Default")
      (node (ref "MICROSD_CARD_HOLDER") (pin "13") (pinfunction "SHELL_13") (pintype "unspecified+no_connect"))
    )
    (net (code "73") (name "unconnected-(RIGHT_PICO_SOCKET-35_-_ADC_VREF-Pad6)") (class "Default")
      (node (ref "RIGHT_PICO_SOCKET") (pin "6") (pinfunction "35_-_ADC_VREF_6") (pintype "unspecified+no_connect"))
    )
    (net (code "74") (name "unconnected-(RIGHT_PICO_SOCKET-37_-_3V3_EN-Pad4)") (class "Default")
      (node (ref "RIGHT_PICO_SOCKET") (pin "4") (pinfunction "37_-_3V3_EN_4") (pintype "unspecified+no_connect"))
    )
    (net (code "75") (name "{slash}LDS") (class "Default")
      (node (ref "ADDR_ROM_SIGNALS") (pin "4") (pinfunction "A3_4") (pintype "unspecified"))
      (node (ref "CON1") (pin "37") (pinfunction "/LDS_37") (pintype "unspecified"))
    )
    (net (code "76") (name "{slash}READ") (class "Default")
      (node (ref "ADDR_BUS_LSB") (pin "19") (pinfunction "OE#_19") (pintype "unspecified"))
      (node (ref "ADDR_BUS_MSB") (pin "19") (pinfunction "OE#_19") (pintype "unspecified"))
      (node (ref "R2") (pin "2") (pinfunction "2_2") (pintype "unspecified"))
      (node (ref "RIGHT_PICO_SOCKET") (pin "9") (pinfunction "32_-_GP27_9") (pintype "unspecified"))
    )
    (net (code "77") (name "{slash}ROM3") (class "Default")
      (node (ref "ADDR_ROM_SIGNALS") (pin "2") (pinfunction "A1_2") (pintype "unspecified"))
      (node (ref "CON1") (pin "31") (pinfunction "/ROM3_31") (pintype "unspecified"))
    )
    (net (code "78") (name "{slash}ROM3_3V3") (class "Default")
      (node (ref "ADDR_ROM_SIGNALS") (pin "18") (pinfunction "B1_18") (pintype "unspecified"))
      (node (ref "RIGHT_PICO_SOCKET") (pin "10") (pinfunction "31_-_GP26_10") (pintype "unspecified"))
    )
    (net (code "79") (name "{slash}ROM4") (class "Default")
      (node (ref "ADDR_ROM_SIGNALS") (pin "3") (pinfunction "A2_3") (pintype "unspecified"))
      (node (ref "CON1") (pin "33") (pinfunction "/ROM4_33") (pintype "unspecified"))
    )
    (net (code "80") (name "{slash}ROM4_3V3") (class "Default")
      (node (ref "ADDR_ROM_SIGNALS") (pin "17") (pinfunction "B2_17") (pintype "unspecified"))
      (node (ref "RIGHT_PICO_SOCKET") (pin "12") (pinfunction "29_-_GP22_12") (pintype "unspecified"))
    )
    (net (code "81") (name "{slash}UDS") (class "Default")
      (node (ref "ADDR_BUS_LSB") (pin "2") (pinfunction "A1_2") (pintype "unspecified"))
      (node (ref "CON1") (pin "35") (pinfunction "/UDS_35") (pintype "unspecified"))
    )
    (net (code "82") (name "{slash}WRITE") (class "Default")
      (node (ref "DATA_BUS_LSB") (pin "19") (pinfunction "OE#_19") (pintype "unspecified"))
      (node (ref "DATA_BUS_MSB") (pin "19") (pinfunction "OE#_19") (pintype "unspecified"))
      (node (ref "R1") (pin "2") (pinfunction "2_2") (pintype "unspecified"))
      (node (ref "RIGHT_PICO_SOCKET") (pin "7") (pinfunction "34_-_GP28_7") (pintype "unspecified"))
    )
  )
)
